# RF_load.net
KiCad netlist of a schematic drawn in Altium Designer
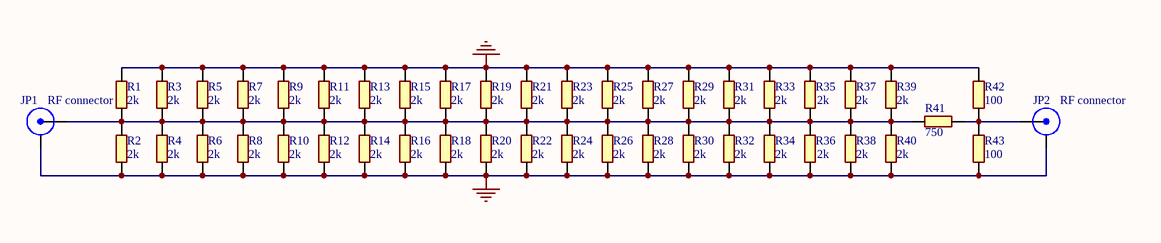
[diagram p0: RF_load.SchDoc]

(export (version "E")
  (design (tool "Eeschema 10.0.6"))
  (components
    (comp (ref "JP1")
      (value "RF connector")
      (footprint "AMPHENOL_132357-11")
      (description "RF Connector")
      (libsource (lib "Connectors") (part "RF connector"))
    )
    (comp (ref "JP2")
      (value "RF connector")
      (footprint "AMPHENOL_132357-11")
      (description "RF Connector")
      (libsource (lib "Connectors") (part "RF connector"))
    )
    (comp (ref "R1") (value "2k") (footprint "R-1206 _narrow") (libsource (lib "Passive") (part "RES")))
    (comp (ref "R2") (value "2k") (footprint "R-1206 _narrow") (libsource (lib "Passive") (part "RES")))
    (comp (ref "R3") (value "2k") (footprint "R-1206 _narrow") (libsource (lib "Passive") (part "RES")))
    (comp (ref "R4") (value "2k") (footprint "R-1206 _narrow") (libsource (lib "Passive") (part "RES")))
    (comp (ref "R5") (value "2k") (footprint "R-1206 _narrow") (libsource (lib "Passive") (part "RES")))
    (comp (ref "R6") (value "2k") (footprint "R-1206 _narrow") (libsource (lib "Passive") (part "RES")))
    (comp (ref "R7") (value "2k") (footprint "R-1206 _narrow") (libsource (lib "Passive") (part "RES")))
    (comp (ref "R8") (value "2k") (footprint "R-1206 _narrow") (libsource (lib "Passive") (part "RES")))
    (comp (ref "R9") (value "2k") (footprint "R-1206 _narrow") (libsource (lib "Passive") (part "RES")))
    (comp (ref "R10") (value "2k") (footprint "R-1206 _narrow") (libsource (lib "Passive") (part "RES")))
    (comp (ref "R11") (value "2k") (footprint "R-1206 _narrow") (libsource (lib "Passive") (part "RES")))
    (comp (ref "R12") (value "2k") (footprint "R-1206 _narrow") (libsource (lib "Passive") (part "RES")))
    (comp (ref "R13") (value "2k") (footprint "R-1206 _narrow") (libsource (lib "Passive") (part "RES")))
    (comp (ref "R14") (value "2k") (footprint "R-1206 _narrow") (libsource (lib "Passive") (part "RES")))
    (comp (ref "R15") (value "2k") (footprint "R-1206 _narrow") (libsource (lib "Passive") (part "RES")))
    (comp (ref "R16") (value "2k") (footprint "R-1206 _narrow") (libsource (lib "Passive") (part "RES")))
    (comp (ref "R17") (value "2k") (footprint "R-1206 _narrow") (libsource (lib "Passive") (part "RES")))
    (comp (ref "R18") (value "2k") (footprint "R-1206 _narrow") (libsource (lib "Passive") (part "RES")))
    (comp (ref "R19") (value "2k") (footprint "R-1206 _narrow") (libsource (lib "Passive") (part "RES")))
    (comp (ref "R20") (value "2k") (footprint "R-1206 _narrow") (libsource (lib "Passive") (part "RES")))
    (comp (ref "R21") (value "2k") (footprint "R-1206 _narrow") (libsource (lib "Passive") (part "RES")))
    (comp (ref "R22") (value "2k") (footprint "R-1206 _narrow") (libsource (lib "Passive") (part "RES")))
    (comp (ref "R23") (value "2k") (footprint "R-1206 _narrow") (libsource (lib "Passive") (part "RES")))
    (comp (ref "R24") (value "2k") (footprint "R-1206 _narrow") (libsource (lib "Passive") (part "RES")))
    (comp (ref "R25") (value "2k") (footprint "R-1206 _narrow") (libsource (lib "Passive") (part "RES")))
    (comp (ref "R26") (value "2k") (footprint "R-1206 _narrow") (libsource (lib "Passive") (part "RES")))
    (comp (ref "R27") (value "2k") (footprint "R-1206 _narrow") (libsource (lib "Passive") (part "RES")))
    (comp (ref "R28") (value "2k") (footprint "R-1206 _narrow") (libsource (lib "Passive") (part "RES")))
    (comp (ref "R29") (value "2k") (footprint "R-1206 _narrow") (libsource (lib "Passive") (part "RES")))
    (comp (ref "R30") (value "2k") (footprint "R-1206 _narrow") (libsource (lib "Passive") (part "RES")))
    (comp (ref "R31") (value "2k") (footprint "R-1206 _narrow") (libsource (lib "Passive") (part "RES")))
    (comp (ref "R32") (value "2k") (footprint "R-1206 _narrow") (libsource (lib "Passive") (part "RES")))
    (comp (ref "R33") (value "2k") (footprint "R-1206 _narrow") (libsource (lib "Passive") (part "RES")))
    (comp (ref "R34") (value "2k") (footprint "R-1206 _narrow") (libsource (lib "Passive") (part "RES")))
    (comp (ref "R35") (value "2k") (footprint "R-1206 _narrow") (libsource (lib "Passive") (part "RES")))
    (comp (ref "R36") (value "2k") (footprint "R-1206 _narrow") (libsource (lib "Passive") (part "RES")))
    (comp (ref "R37") (value "2k") (footprint "R-1206 _narrow") (libsource (lib "Passive") (part "RES")))
    (comp (ref "R38") (value "2k") (footprint "R-1206 _narrow") (libsource (lib "Passive") (part "RES")))
    (comp (ref "R39") (value "2k") (footprint "R-1206 _narrow") (libsource (lib "Passive") (part "RES")))
    (comp (ref "R40") (value "2k") (footprint "R-1206 _narrow") (libsource (lib "Passive") (part "RES")))
    (comp (ref "R41") (value "750") (footprint "R-1206 _narrow") (libsource (lib "") (part "RES_1")))
    (comp (ref "R42") (value "100") (footprint "R-1206 _narrow") (libsource (lib "Passive") (part "RES")))
    (comp (ref "R43") (value "100") (footprint "R-1206 _narrow") (libsource (lib "Passive") (part "RES")))
  )
  (nets
    (net (code "1") (name "GND") (class "Default")
      (node (ref "JP1") (pin "2") (pinfunction "Y_2") (pintype "passive"))
      (node (ref "JP2") (pin "2") (pinfunction "Y_2") (pintype "passive"))
      (node (ref "R1") (pin "2") (pinfunction "2_2") (pintype "passive"))
      (node (ref "R10") (pin "1") (pinfunction "1_1") (pintype "passive"))
      (node (ref "R11") (pin "2") (pinfunction "2_2") (pintype "passive"))
      (node (ref "R12") (pin "1") (pinfunction "1_1") (pintype "passive"))
      (node (ref "R13") (pin "2") (pinfunction "2_2") (pintype "passive"))
      (node (ref "R14") (pin "1") (pinfunction "1_1") (pintype "passive"))
      (node (ref "R15") (pin "2") (pinfunction "2_2") (pintype "passive"))
      (node (ref "R16") (pin "1") (pinfunction "1_1") (pintype "passive"))
      (node (ref "R17") (pin "2") (pinfunction "2_2") (pintype "passive"))
      (node (ref "R18") (pin "1") (pinfunction "1_1") (pintype "passive"))
      (node (ref "R19") (pin "2") (pinfunction "2_2") (pintype "passive"))
      (node (ref "R2") (pin "1") (pinfunction "1_1") (pintype "passive"))
      (node (ref "R20") (pin "1") (pinfunction "1_1") (pintype "passive"))
      (node (ref "R21") (pin "2") (pinfunction "2_2") (pintype "passive"))
      (node (ref "R22") (pin "1") (pinfunction "1_1") (pintype "passive"))
      (node (ref "R23") (pin "2") (pinfunction "2_2") (pintype "passive"))
      (node (ref "R24") (pin "1") (pinfunction "1_1") (pintype "passive"))
      (node (ref "R25") (pin "2") (pinfunction "2_2") (pintype "passive"))
      (node (ref "R26") (pin "1") (pinfunction "1_1") (pintype "passive"))
      (node (ref "R27") (pin "2") (pinfunction "2_2") (pintype "passive"))
      (node (ref "R28") (pin "1") (pinfunction "1_1") (pintype "passive"))
      (node (ref "R29") (pin "2") (pinfunction "2_2") (pintype "passive"))
      (node (ref "R3") (pin "2") (pinfunction "2_2") (pintype "passive"))
      (node (ref "R30") (pin "1") (pinfunction "1_1") (pintype "passive"))
      (node (ref "R31") (pin "2") (pinfunction "2_2") (pintype "passive"))
      (node (ref "R32") (pin "1") (pinfunction "1_1") (pintype "passive"))
      (node (ref "R33") (pin "2") (pinfunction "2_2") (pintype "passive"))
      (node (ref "R34") (pin "1") (pinfunction "1_1") (pintype "passive"))
      (node (ref "R35") (pin "2") (pinfunction "2_2") (pintype "passive"))
      (node (ref "R36") (pin "1") (pinfunction "1_1") (pintype "passive"))
      (node (ref "R37") (pin "2") (pinfunction "2_2") (pintype "passive"))
      (node (ref "R38") (pin "1") (pinfunction "1_1") (pintype "passive"))
      (node (ref "R39") (pin "2") (pinfunction "2_2") (pintype "passive"))
      (node (ref "R4") (pin "1") (pinfunction "1_1") (pintype "passive"))
      (node (ref "R40") (pin "1") (pinfunction "1_1") (pintype "passive"))
      (node (ref "R42") (pin "2") (pinfunction "2_2") (pintype "passive"))
      (node (ref "R43") (pin "1") (pinfunction "1_1") (pintype "passive"))
      (node (ref "R5") (pin "2") (pinfunction "2_2") (pintype "passive"))
      (node (ref "R6") (pin "1") (pinfunction "1_1") (pintype "passive"))
      (node (ref "R7") (pin "2") (pinfunction "2_2") (pintype "passive"))
      (node (ref "R8") (pin "1") (pinfunction "1_1") (pintype "passive"))
      (node (ref "R9") (pin "2") (pinfunction "2_2") (pintype "passive"))
    )
    (net (code "2") (name "Net-(JP1-X)") (class "Default")
      (node (ref "JP1") (pin "1") (pinfunction "X_1") (pintype "passive"))
      (node (ref "R1") (pin "1") (pinfunction "1_1") (pintype "passive"))
      (node (ref "R10") (pin "2") (pinfunction "2_2") (pintype "passive"))
      (node (ref "R11") (pin "1") (pinfunction "1_1") (pintype "passive"))
      (node (ref "R12") (pin "2") (pinfunction "2_2") (pintype "passive"))
      (node (ref "R13") (pin "1") (pinfunction "1_1") (pintype "passive"))
      (node (ref "R14") (pin "2") (pinfunction "2_2") (pintype "passive"))
      (node (ref "R15") (pin "1") (pinfunction "1_1") (pintype "passive"))
      (node (ref "R16") (pin "2") (pinfunction "2_2") (pintype "passive"))
      (node (ref "R17") (pin "1") (pinfunction "1_1") (pintype "passive"))
      (node (ref "R18") (pin "2") (pinfunction "2_2") (pintype "passive"))
      (node (ref "R19") (pin "1") (pinfunction "1_1") (pintype "passive"))
      (node (ref "R2") (pin "2") (pinfunction "2_2") (pintype "passive"))
      (node (ref "R20") (pin "2") (pinfunction "2_2") (pintype "passive"))
      (node (ref "R21") (pin "1") (pinfunction "1_1") (pintype "passive"))
      (node (ref "R22") (pin "2") (pinfunction "2_2") (pintype "passive"))
      (node (ref "R23") (pin "1") (pinfunction "1_1") (pintype "passive"))
      (node (ref "R24") (pin "2") (pinfunction "2_2") (pintype "passive"))
      (node (ref "R25") (pin "1") (pinfunction "1_1") (pintype "passive"))
      (node (ref "R26") (pin "2") (pinfunction "2_2") (pintype "passive"))
      (node (ref "R27") (pin "1") (pinfunction "1_1") (pintype "passive"))
      (node (ref "R28") (pin "2") (pinfunction "2_2") (pintype "passive"))
      (node (ref "R29") (pin "1") (pinfunction "1_1") (pintype "passive"))
      (node (ref "R3") (pin "1") (pinfunction "1_1") (pintype "passive"))
      (node (ref "R30") (pin "2") (pinfunction "2_2") (pintype "passive"))
      (node (ref "R31") (pin "1") (pinfunction "1_1") (pintype "passive"))
      (node (ref "R32") (pin "2") (pinfunction "2_2") (pintype "passive"))
      (node (ref "R33") (pin "1") (pinfunction "1_1") (pintype "passive"))
      (node (ref "R34") (pin "2") (pinfunction "2_2") (pintype "passive"))
      (node (ref "R35") (pin "1") (pinfunction "1_1") (pintype "passive"))
      (node (ref "R36") (pin "2") (pinfunction "2_2") (pintype "passive"))
      (node (ref "R37") (pin "1") (pinfunction "1_1") (pintype "passive"))
      (node (ref "R38") (pin "2") (pinfunction "2_2") (pintype "passive"))
      (node (ref "R39") (pin "1") (pinfunction "1_1") (pintype "passive"))
      (node (ref "R4") (pin "2") (pinfunction "2_2") (pintype "passive"))
      (node (ref "R40") (pin "2") (pinfunction "2_2") (pintype "passive"))
      (node (ref "R41") (pin "2") (pinfunction "2_2") (pintype "passive"))
      (node (ref "R5") (pin "1") (pinfunction "1_1") (pintype "passive"))
      (node (ref "R6") (pin "2") (pinfunction "2_2") (pintype "passive"))
      (node (ref "R7") (pin "1") (pinfunction "1_1") (pintype "passive"))
      (node (ref "R8") (pin "2") (pinfunction "2_2") (pintype "passive"))
      (node (ref "R9") (pin "1") (pinfunction "1_1") (pintype "passive"))
    )
    (net (code "3") (name "Net-(JP2-X)") (class "Default")
      (node (ref "JP2") (pin "1") (pinfunction "X_1") (pintype "passive"))
      (node (ref "R41") (pin "1") (pinfunction "1_1") (pintype "passive"))
      (node (ref "R42") (pin "1") (pinfunction "1_1") (pintype "passive"))
      (node (ref "R43") (pin "2") (pinfunction "2_2") (pintype "passive"))
    )
  )
)
